# RPi_SPI_inputs_v03.net
KiCad netlist of a schematic drawn in EAGLE
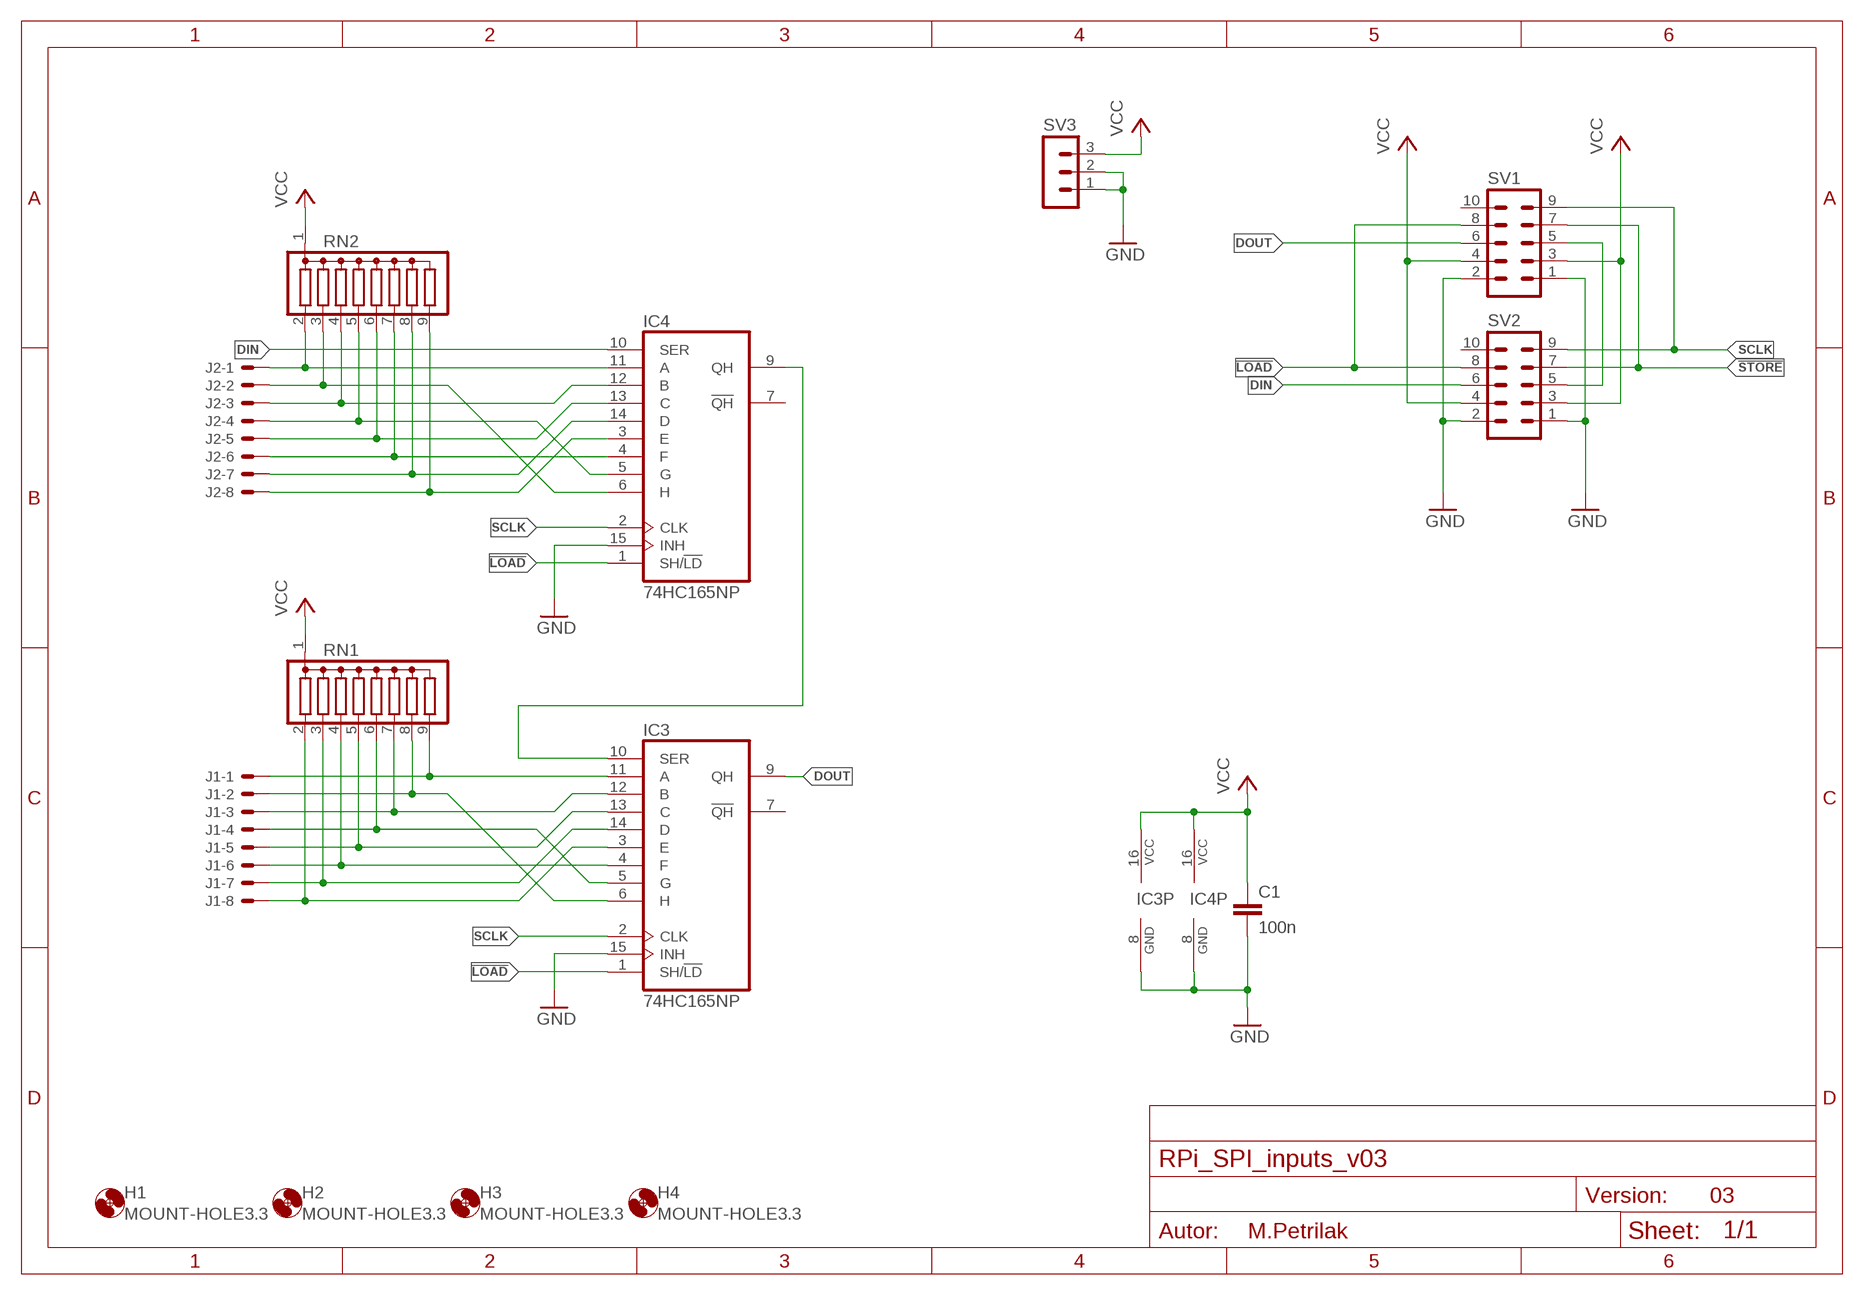
[diagram p0: schematic, sheet 1]

(export (version "E")
  (design (tool "Eeschema 10.0.6"))
  (components
    (comp (ref "C1")
      (value "100n")
      (footprint "eagle-import:C1206")
      (libsource (lib "eagle-import") (part "C-EUC1206"))
    )
    (comp (ref "H1")
      (value "MOUNT-HOLE3.3")
      (footprint "eagle-import:3,3")
      (libsource (lib "eagle-import") (part "MOUNT-HOLE3.3"))
    )
    (comp (ref "H2")
      (value "MOUNT-HOLE3.3")
      (footprint "eagle-import:3,3")
      (libsource (lib "eagle-import") (part "MOUNT-HOLE3.3"))
    )
    (comp (ref "H3")
      (value "MOUNT-HOLE3.3")
      (footprint "eagle-import:3,3")
      (libsource (lib "eagle-import") (part "MOUNT-HOLE3.3"))
    )
    (comp (ref "H4")
      (value "MOUNT-HOLE3.3")
      (footprint "eagle-import:3,3")
      (libsource (lib "eagle-import") (part "MOUNT-HOLE3.3"))
    )
    (comp (ref "IC3")
      (value "74HC165NP")
      (footprint "eagle-import:SOCKET-16")
      (libsource (lib "eagle-import") (part "74165NPHC"))
    )
    (comp (ref "IC4")
      (value "74HC165NP")
      (footprint "eagle-import:SOCKET-16")
      (libsource (lib "eagle-import") (part "74165NPHC"))
    )
    (comp (ref "J1")
      (value "22-05-7088-SPEC-08")
      (footprint "eagle-import:7395-08_SPEC")
      (libsource (lib "eagle-import") (part "22-?-0805-7088-SPEC"))
    )
    (comp (ref "J2")
      (value "22-05-7088-SPEC-08")
      (footprint "eagle-import:7395-08_SPEC")
      (libsource (lib "eagle-import") (part "22-?-0805-7088-SPEC"))
    )
    (comp (ref "RN1")
      (value "G08R")
      (footprint "eagle-import:SIL9")
      (libsource (lib "eagle-import") (part "G08R"))
    )
    (comp (ref "RN2")
      (value "G08R")
      (footprint "eagle-import:SIL9")
      (libsource (lib "eagle-import") (part "G08R"))
    )
    (comp (ref "SV1")
      (value "ML10")
      (footprint "eagle-import:ML10")
      (libsource (lib "eagle-import") (part "ML10"))
    )
    (comp (ref "SV2")
      (value "ML10")
      (footprint "eagle-import:ML10")
      (libsource (lib "eagle-import") (part "ML10"))
    )
    (comp (ref "SV3")
      (value "MA03-1_NO")
      (footprint "eagle-import:MA03-1_NO")
      (libsource (lib "eagle-import") (part "MA03-1_NO"))
    )
  )
  (nets
    (net (code "1") (name "/~{LOAD}") (class "Default")
      (node (ref "IC3") (pin "1") (pinfunction "SH/~{LD}_1") (pintype "input"))
      (node (ref "IC4") (pin "1") (pinfunction "SH/~{LD}_1") (pintype "input"))
      (node (ref "SV1") (pin "8") (pinfunction "8_8") (pintype "passive"))
      (node (ref "SV2") (pin "8") (pinfunction "8_8") (pintype "passive"))
    )
    (net (code "2") (name "/~{STORE}") (class "Default")
      (node (ref "SV1") (pin "7") (pinfunction "7_7") (pintype "passive"))
      (node (ref "SV2") (pin "7") (pinfunction "7_7") (pintype "passive"))
    )
    (net (code "3") (name "DIN") (class "Default")
      (node (ref "IC4") (pin "10") (pinfunction "SER_10") (pintype "input"))
      (node (ref "SV2") (pin "6") (pinfunction "6_6") (pintype "passive"))
    )
    (net (code "4") (name "DOUT") (class "Default")
      (node (ref "IC3") (pin "9") (pinfunction "QH_9") (pintype "output"))
      (node (ref "SV1") (pin "6") (pinfunction "6_6") (pintype "passive"))
    )
    (net (code "5") (name "GND") (class "Default")
      (node (ref "C1") (pin "2") (pinfunction "2_2") (pintype "passive"))
      (node (ref "IC3") (pin "15") (pinfunction "INH_15") (pintype "input"))
      (node (ref "IC3") (pin "8") (pinfunction "GND_8") (pintype "power_in"))
      (node (ref "IC4") (pin "15") (pinfunction "INH_15") (pintype "input"))
      (node (ref "IC4") (pin "8") (pinfunction "GND_8") (pintype "power_in"))
      (node (ref "SV1") (pin "1") (pinfunction "1_1") (pintype "passive"))
      (node (ref "SV1") (pin "2") (pinfunction "2_2") (pintype "passive"))
      (node (ref "SV2") (pin "1") (pinfunction "1_1") (pintype "passive"))
      (node (ref "SV2") (pin "2") (pinfunction "2_2") (pintype "passive"))
      (node (ref "SV3") (pin "1") (pinfunction "1_1") (pintype "passive"))
      (node (ref "SV3") (pin "2") (pinfunction "2_2") (pintype "passive"))
    )
    (net (code "6") (name "Net-(IC3A-A)") (class "Default")
      (node (ref "IC3") (pin "11") (pinfunction "A_11") (pintype "input"))
      (node (ref "J1") (pin "1") (pinfunction "S_1") (pintype "passive"))
      (node (ref "RN1") (pin "9") (pinfunction "9_9") (pintype "passive"))
    )
    (net (code "7") (name "Net-(IC3A-B)") (class "Default")
      (node (ref "IC3") (pin "12") (pinfunction "B_12") (pintype "input"))
      (node (ref "J1") (pin "3") (pinfunction "S_3") (pintype "passive"))
      (node (ref "RN1") (pin "7") (pinfunction "7_7") (pintype "passive"))
    )
    (net (code "8") (name "Net-(IC3A-C)") (class "Default")
      (node (ref "IC3") (pin "13") (pinfunction "C_13") (pintype "input"))
      (node (ref "J1") (pin "5") (pinfunction "S_5") (pintype "passive"))
      (node (ref "RN1") (pin "5") (pinfunction "5_5") (pintype "passive"))
    )
    (net (code "9") (name "Net-(IC3A-D)") (class "Default")
      (node (ref "IC3") (pin "14") (pinfunction "D_14") (pintype "input"))
      (node (ref "J1") (pin "7") (pinfunction "S_7") (pintype "passive"))
      (node (ref "RN1") (pin "3") (pinfunction "3_3") (pintype "passive"))
    )
    (net (code "10") (name "Net-(IC3A-E)") (class "Default")
      (node (ref "IC3") (pin "3") (pinfunction "E_3") (pintype "input"))
      (node (ref "J1") (pin "8") (pinfunction "S_8") (pintype "passive"))
      (node (ref "RN1") (pin "2") (pinfunction "2_2") (pintype "passive"))
    )
    (net (code "11") (name "Net-(IC3A-F)") (class "Default")
      (node (ref "IC3") (pin "4") (pinfunction "F_4") (pintype "input"))
      (node (ref "J1") (pin "6") (pinfunction "S_6") (pintype "passive"))
      (node (ref "RN1") (pin "4") (pinfunction "4_4") (pintype "passive"))
    )
    (net (code "12") (name "Net-(IC3A-G)") (class "Default")
      (node (ref "IC3") (pin "5") (pinfunction "G_5") (pintype "input"))
      (node (ref "J1") (pin "4") (pinfunction "S_4") (pintype "passive"))
      (node (ref "RN1") (pin "6") (pinfunction "6_6") (pintype "passive"))
    )
    (net (code "13") (name "Net-(IC3A-H)") (class "Default")
      (node (ref "IC3") (pin "6") (pinfunction "H_6") (pintype "input"))
      (node (ref "J1") (pin "2") (pinfunction "S_2") (pintype "passive"))
      (node (ref "RN1") (pin "8") (pinfunction "8_8") (pintype "passive"))
    )
    (net (code "14") (name "Net-(IC3A-SER)") (class "Default")
      (node (ref "IC3") (pin "10") (pinfunction "SER_10") (pintype "input"))
      (node (ref "IC4") (pin "9") (pinfunction "QH_9") (pintype "output"))
    )
    (net (code "15") (name "Net-(IC4A-A)") (class "Default")
      (node (ref "IC4") (pin "11") (pinfunction "A_11") (pintype "input"))
      (node (ref "J2") (pin "1") (pinfunction "S_1") (pintype "passive"))
      (node (ref "RN2") (pin "2") (pinfunction "2_2") (pintype "passive"))
    )
    (net (code "16") (name "Net-(IC4A-B)") (class "Default")
      (node (ref "IC4") (pin "12") (pinfunction "B_12") (pintype "input"))
      (node (ref "J2") (pin "3") (pinfunction "S_3") (pintype "passive"))
      (node (ref "RN2") (pin "4") (pinfunction "4_4") (pintype "passive"))
    )
    (net (code "17") (name "Net-(IC4A-C)") (class "Default")
      (node (ref "IC4") (pin "13") (pinfunction "C_13") (pintype "input"))
      (node (ref "J2") (pin "5") (pinfunction "S_5") (pintype "passive"))
      (node (ref "RN2") (pin "6") (pinfunction "6_6") (pintype "passive"))
    )
    (net (code "18") (name "Net-(IC4A-D)") (class "Default")
      (node (ref "IC4") (pin "14") (pinfunction "D_14") (pintype "input"))
      (node (ref "J2") (pin "7") (pinfunction "S_7") (pintype "passive"))
      (node (ref "RN2") (pin "8") (pinfunction "8_8") (pintype "passive"))
    )
    (net (code "19") (name "Net-(IC4A-E)") (class "Default")
      (node (ref "IC4") (pin "3") (pinfunction "E_3") (pintype "input"))
      (node (ref "J2") (pin "8") (pinfunction "S_8") (pintype "passive"))
      (node (ref "RN2") (pin "9") (pinfunction "9_9") (pintype "passive"))
    )
    (net (code "20") (name "Net-(IC4A-F)") (class "Default")
      (node (ref "IC4") (pin "4") (pinfunction "F_4") (pintype "input"))
      (node (ref "J2") (pin "6") (pinfunction "S_6") (pintype "passive"))
      (node (ref "RN2") (pin "7") (pinfunction "7_7") (pintype "passive"))
    )
    (net (code "21") (name "Net-(IC4A-G)") (class "Default")
      (node (ref "IC4") (pin "5") (pinfunction "G_5") (pintype "input"))
      (node (ref "J2") (pin "4") (pinfunction "S_4") (pintype "passive"))
      (node (ref "RN2") (pin "5") (pinfunction "5_5") (pintype "passive"))
    )
    (net (code "22") (name "Net-(IC4A-H)") (class "Default")
      (node (ref "IC4") (pin "6") (pinfunction "H_6") (pintype "input"))
      (node (ref "J2") (pin "2") (pinfunction "S_2") (pintype "passive"))
      (node (ref "RN2") (pin "3") (pinfunction "3_3") (pintype "passive"))
    )
    (net (code "23") (name "Net-(SV1-Pad5)") (class "Default")
      (node (ref "SV1") (pin "5") (pinfunction "5_5") (pintype "passive"))
      (node (ref "SV2") (pin "5") (pinfunction "5_5") (pintype "passive"))
    )
    (net (code "24") (name "SCLK") (class "Default")
      (node (ref "IC3") (pin "2") (pinfunction "CLK_2") (pintype "input"))
      (node (ref "IC4") (pin "2") (pinfunction "CLK_2") (pintype "input"))
      (node (ref "SV1") (pin "9") (pinfunction "9_9") (pintype "passive"))
      (node (ref "SV2") (pin "9") (pinfunction "9_9") (pintype "passive"))
    )
    (net (code "25") (name "VCC") (class "Default")
      (node (ref "C1") (pin "1") (pinfunction "1_1") (pintype "passive"))
      (node (ref "IC3") (pin "16") (pinfunction "VCC_16") (pintype "power_in"))
      (node (ref "IC4") (pin "16") (pinfunction "VCC_16") (pintype "power_in"))
      (node (ref "RN1") (pin "1") (pinfunction "1_1") (pintype "passive"))
      (node (ref "RN2") (pin "1") (pinfunction "1_1") (pintype "passive"))
      (node (ref "SV1") (pin "3") (pinfunction "3_3") (pintype "passive"))
      (node (ref "SV1") (pin "4") (pinfunction "4_4") (pintype "passive"))
      (node (ref "SV2") (pin "3") (pinfunction "3_3") (pintype "passive"))
      (node (ref "SV2") (pin "4") (pinfunction "4_4") (pintype "passive"))
      (node (ref "SV3") (pin "3") (pinfunction "3_3") (pintype "passive"))
    )
    (net (code "26") (name "unconnected-(IC3A-~{QH}-Pad7)") (class "Default")
      (node (ref "IC3") (pin "7") (pinfunction "~{QH}_7") (pintype "output"))
    )
    (net (code "27") (name "unconnected-(IC4A-~{QH}-Pad7)") (class "Default")
      (node (ref "IC4") (pin "7") (pinfunction "~{QH}_7") (pintype "output"))
    )
    (net (code "28") (name "unconnected-(SV1-Pad10)") (class "Default")
      (node (ref "SV1") (pin "10") (pinfunction "10_10") (pintype "passive"))
    )
    (net (code "29") (name "unconnected-(SV2-Pad10)") (class "Default")
      (node (ref "SV2") (pin "10") (pinfunction "10_10") (pintype "passive"))
    )
  )
)
